# AC_nest.net
KiCad netlist of a schematic drawn in EAGLE
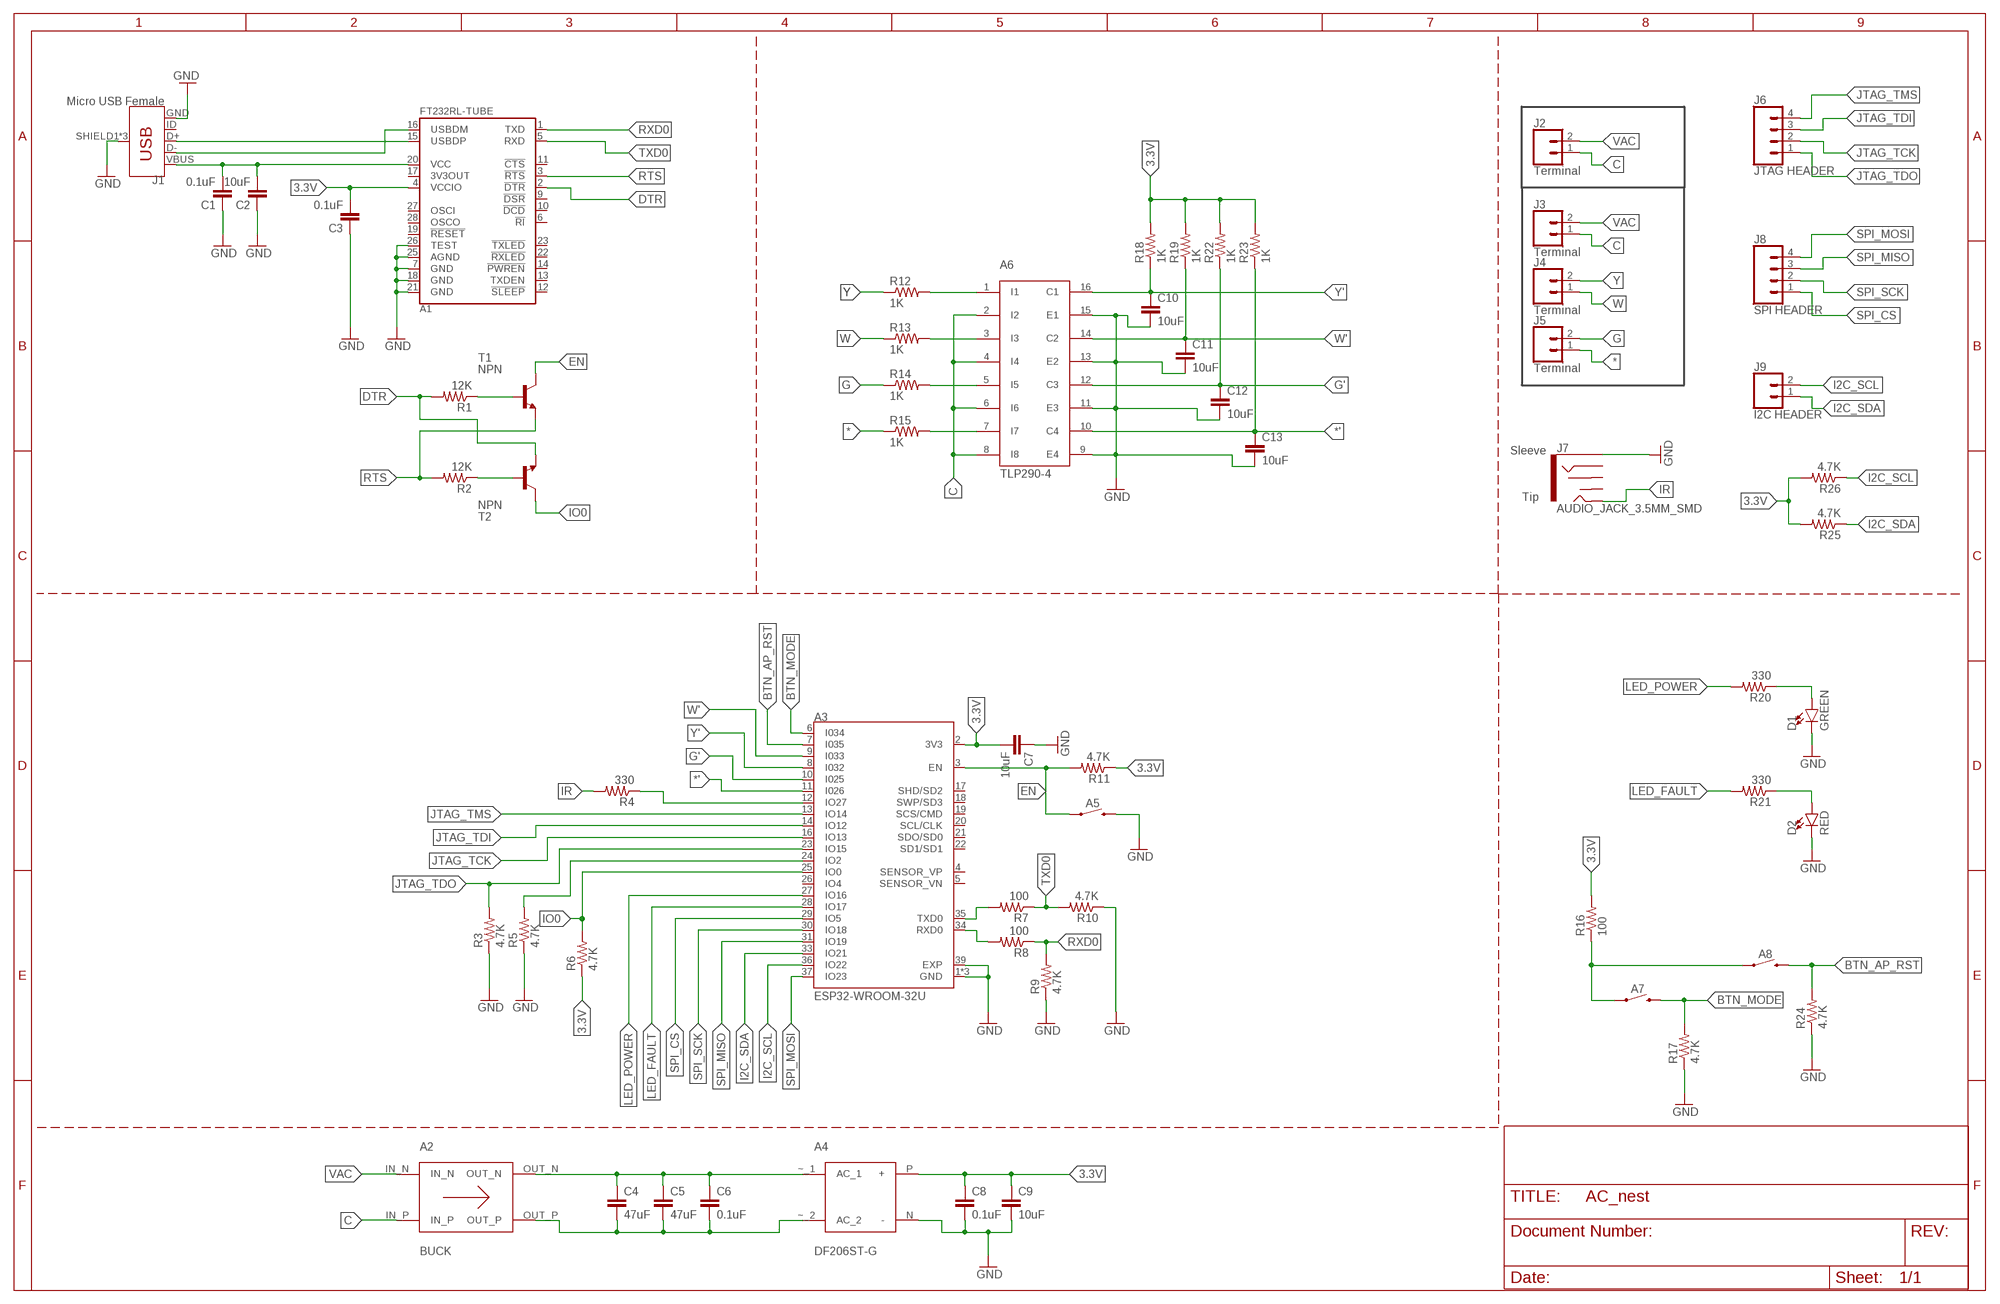
[diagram p0: schematic, sheet 1]

(export (version "E")
  (design (tool "Eeschema 10.0.6"))
  (components
    (comp (ref "A1")
      (value "FT232RL")
      (footprint "eagle-import:SSOP28-LD")
      (fields (field (name "MF") "FTDI,") (field (name "MP") "FT232RL-TUBE"))
      (libsource (lib "eagle-import") (part "FT232RL"))
    )
    (comp (ref "A2")
      (value "BUCK")
      (footprint "eagle-import:BUCK")
      (libsource (lib "eagle-import") (part "BUCK"))
    )
    (comp (ref "A3")
      (value "ESP32-WROOM-32U")
      (footprint "eagle-import:XCVR_ESP32-WROOM-32U")
      (fields (field (name "MF") "Espressif Systems"))
      (libsource (lib "eagle-import") (part "ESP32-WROOM-32U"))
    )
    (comp (ref "A4")
      (value "DF206ST-G")
      (footprint "eagle-import:DF206ST-G")
      (libsource (lib "eagle-import") (part "DF206ST-G"))
    )
    (comp (ref "A5")
      (value "TL3302AF180QJ")
      (footprint "eagle-import:TL3302AF180QJ")
      (libsource (lib "eagle-import") (part "TL3302AF180QJ"))
    )
    (comp (ref "A6")
      (value "TLP290-4")
      (footprint "eagle-import:TLP290-4")
      (libsource (lib "eagle-import") (part "TLP290-4"))
    )
    (comp (ref "A7")
      (value "TL3302AF180QJ")
      (footprint "eagle-import:TL3302AF180QJ")
      (libsource (lib "eagle-import") (part "TL3302AF180QJ"))
    )
    (comp (ref "A8")
      (value "TL3302AF180QJ")
      (footprint "eagle-import:TL3302AF180QJ")
      (libsource (lib "eagle-import") (part "TL3302AF180QJ"))
    )
    (comp (ref "C1")
      (value "0.1uF")
      (footprint "eagle-import:C0603")
      (libsource (lib "eagle-import") (part "C-EUC0603"))
    )
    (comp (ref "C2")
      (value "10uF")
      (footprint "eagle-import:C0603")
      (libsource (lib "eagle-import") (part "C-EUC0603"))
    )
    (comp (ref "C3")
      (value "0.1uF")
      (footprint "eagle-import:C0603")
      (libsource (lib "eagle-import") (part "C-EUC0603"))
    )
    (comp (ref "C4")
      (value "47uF")
      (footprint "eagle-import:C0603")
      (libsource (lib "eagle-import") (part "C-EUC0603"))
    )
    (comp (ref "C5")
      (value "47uF")
      (footprint "eagle-import:C0603")
      (libsource (lib "eagle-import") (part "C-EUC0603"))
    )
    (comp (ref "C6")
      (value "0.1uF")
      (footprint "eagle-import:C0603")
      (libsource (lib "eagle-import") (part "C-EUC0603"))
    )
    (comp (ref "C7")
      (value "10uF")
      (footprint "eagle-import:C0603")
      (libsource (lib "eagle-import") (part "C-EUC0603"))
    )
    (comp (ref "C8")
      (value "0.1uF")
      (footprint "eagle-import:C0603")
      (libsource (lib "eagle-import") (part "C-EUC0603"))
    )
    (comp (ref "C9")
      (value "10uF")
      (footprint "eagle-import:C0603")
      (libsource (lib "eagle-import") (part "C-EUC0603"))
    )
    (comp (ref "C10")
      (value "10uF")
      (footprint "eagle-import:C0603")
      (libsource (lib "eagle-import") (part "C-EUC0603"))
    )
    (comp (ref "C11")
      (value "10uF")
      (footprint "eagle-import:C0603")
      (libsource (lib "eagle-import") (part "C-EUC0603"))
    )
    (comp (ref "C12")
      (value "10uF")
      (footprint "eagle-import:C0603")
      (libsource (lib "eagle-import") (part "C-EUC0603"))
    )
    (comp (ref "C13")
      (value "10uF")
      (footprint "eagle-import:C0603")
      (libsource (lib "eagle-import") (part "C-EUC0603"))
    )
    (comp (ref "D1")
      (value "GREEN")
      (footprint "eagle-import:LED-0603")
      (libsource (lib "eagle-import") (part "LED-GREEN0603"))
    )
    (comp (ref "D2")
      (value "RED")
      (footprint "eagle-import:LED-0603")
      (libsource (lib "eagle-import") (part "LED-RED0603"))
    )
    (comp (ref "J1")
      (value "Micro USB Female")
      (footprint "eagle-import:USB-B-MICRO-SMD")
      (libsource (lib "eagle-import") (part "USB_MICRO-B_FEMALE-SMT"))
    )
    (comp (ref "J2")
      (value "Terminal")
      (footprint "eagle-import:SCREWTERMINAL-3.5MM-2")
      (libsource (lib "eagle-import") (part "CONN_023.5MM"))
    )
    (comp (ref "J3")
      (value "Terminal")
      (footprint "eagle-import:SCREWTERMINAL-3.5MM-2")
      (libsource (lib "eagle-import") (part "CONN_023.5MM"))
    )
    (comp (ref "J4")
      (value "Terminal")
      (footprint "eagle-import:SCREWTERMINAL-3.5MM-2")
      (libsource (lib "eagle-import") (part "CONN_023.5MM"))
    )
    (comp (ref "J5")
      (value "Terminal")
      (footprint "eagle-import:SCREWTERMINAL-3.5MM-2")
      (libsource (lib "eagle-import") (part "CONN_023.5MM"))
    )
    (comp (ref "J6")
      (value "JTAG HEADER")
      (footprint "eagle-import:1X04")
      (libsource (lib "eagle-import") (part "CONN_04"))
    )
    (comp (ref "J7")
      (value "AUDIO_JACK_3.5MM_SMD")
      (footprint "eagle-import:AUDIO-JACK-3.5MM-SMD")
      (libsource (lib "eagle-import") (part "AUDIO_JACK_3.5MM_SMD"))
    )
    (comp (ref "J8")
      (value "SPI HEADER")
      (footprint "eagle-import:1X04")
      (libsource (lib "eagle-import") (part "SparkFun-Connectors_513_CONN_04"))
    )
    (comp (ref "J9")
      (value "I2C HEADER")
      (footprint "eagle-import:1X02")
      (libsource (lib "eagle-import") (part "CONN_02"))
    )
    (comp (ref "R1")
      (value "12K")
      (footprint "eagle-import:R0603")
      (libsource (lib "eagle-import") (part "R-US_R0603"))
    )
    (comp (ref "R2")
      (value "12K")
      (footprint "eagle-import:R0603")
      (libsource (lib "eagle-import") (part "R-US_R0603"))
    )
    (comp (ref "R3")
      (value "4.7K")
      (footprint "eagle-import:R0603")
      (libsource (lib "eagle-import") (part "R-US_R0603"))
    )
    (comp (ref "R4")
      (value "330")
      (footprint "eagle-import:R0603")
      (libsource (lib "eagle-import") (part "R-US_R0603"))
    )
    (comp (ref "R5")
      (value "4.7K")
      (footprint "eagle-import:R0603")
      (libsource (lib "eagle-import") (part "R-US_R0603"))
    )
    (comp (ref "R6")
      (value "4.7K")
      (footprint "eagle-import:R0603")
      (libsource (lib "eagle-import") (part "R-US_R0603"))
    )
    (comp (ref "R7")
      (value "100")
      (footprint "eagle-import:R0603")
      (libsource (lib "eagle-import") (part "R-US_R0603"))
    )
    (comp (ref "R8")
      (value "100")
      (footprint "eagle-import:R0603")
      (libsource (lib "eagle-import") (part "R-US_R0603"))
    )
    (comp (ref "R9")
      (value "4.7K")
      (footprint "eagle-import:R0603")
      (libsource (lib "eagle-import") (part "R-US_R0603"))
    )
    (comp (ref "R10")
      (value "4.7K")
      (footprint "eagle-import:R0603")
      (libsource (lib "eagle-import") (part "R-US_R0603"))
    )
    (comp (ref "R11")
      (value "4.7K")
      (footprint "eagle-import:R0603")
      (libsource (lib "eagle-import") (part "R-US_R0603"))
    )
    (comp (ref "R12")
      (value "1K")
      (footprint "eagle-import:R0603")
      (libsource (lib "eagle-import") (part "R-US_R0603"))
    )
    (comp (ref "R13")
      (value "1K")
      (footprint "eagle-import:R0603")
      (libsource (lib "eagle-import") (part "R-US_R0603"))
    )
    (comp (ref "R14")
      (value "1K")
      (footprint "eagle-import:R0603")
      (libsource (lib "eagle-import") (part "R-US_R0603"))
    )
    (comp (ref "R15")
      (value "1K")
      (footprint "eagle-import:R0603")
      (libsource (lib "eagle-import") (part "R-US_R0603"))
    )
    (comp (ref "R16")
      (value "100")
      (footprint "eagle-import:R0603")
      (libsource (lib "eagle-import") (part "R-US_R0603"))
    )
    (comp (ref "R17")
      (value "4.7K")
      (footprint "eagle-import:R0603")
      (libsource (lib "eagle-import") (part "R-US_R0603"))
    )
    (comp (ref "R18")
      (value "1K")
      (footprint "eagle-import:R0603")
      (libsource (lib "eagle-import") (part "R-US_R0603"))
    )
    (comp (ref "R19")
      (value "1K")
      (footprint "eagle-import:R0603")
      (libsource (lib "eagle-import") (part "R-US_R0603"))
    )
    (comp (ref "R20")
      (value "330")
      (footprint "eagle-import:R0603")
      (libsource (lib "eagle-import") (part "R-US_R0603"))
    )
    (comp (ref "R21")
      (value "330")
      (footprint "eagle-import:R0603")
      (libsource (lib "eagle-import") (part "R-US_R0603"))
    )
    (comp (ref "R22")
      (value "1K")
      (footprint "eagle-import:R0603")
      (libsource (lib "eagle-import") (part "R-US_R0603"))
    )
    (comp (ref "R23")
      (value "1K")
      (footprint "eagle-import:R0603")
      (libsource (lib "eagle-import") (part "R-US_R0603"))
    )
    (comp (ref "R24")
      (value "4.7K")
      (footprint "eagle-import:R0603")
      (libsource (lib "eagle-import") (part "R-US_R0603"))
    )
    (comp (ref "R25")
      (value "4.7K")
      (footprint "eagle-import:R0603")
      (libsource (lib "eagle-import") (part "R-US_R0603"))
    )
    (comp (ref "R26")
      (value "4.7K")
      (footprint "eagle-import:R0603")
      (libsource (lib "eagle-import") (part "R-US_R0603"))
    )
    (comp (ref "T1")
      (value "NPN")
      (footprint "eagle-import:SOT23-EBC")
      (libsource (lib "eagle-import") (part "-NPN-SOT23-EBC"))
    )
    (comp (ref "T2")
      (value "NPN")
      (footprint "eagle-import:SOT23-EBC")
      (libsource (lib "eagle-import") (part "-NPN-SOT23-EBC"))
    )
  )
  (nets
    (net (code "1") (name "*") (class "Default")
      (node (ref "J5") (pin "1") (pinfunction "1_1") (pintype "passive"))
      (node (ref "R15") (pin "1") (pinfunction "1_1") (pintype "passive"))
    )
    (net (code "2") (name "*'") (class "Default")
      (node (ref "A3") (pin "11") (pinfunction "I026_11") (pintype "bidirectional"))
      (node (ref "A6") (pin "10") (pinfunction "C4_10") (pintype "bidirectional"))
      (node (ref "C13") (pin "1") (pinfunction "1_1") (pintype "passive"))
      (node (ref "R23") (pin "1") (pinfunction "1_1") (pintype "passive"))
    )
    (net (code "3") (name "/3V3OUT") (class "Default")
      (node (ref "A1") (pin "17") (pinfunction "3V3OUT_17") (pintype "power_in"))
    )
    (net (code "4") (name "3.3V") (class "Default")
      (node (ref "A1") (pin "4") (pinfunction "VCCIO_4") (pintype "power_in"))
      (node (ref "A3") (pin "2") (pinfunction "3V3_2") (pintype "power_in"))
      (node (ref "A4") (pin "P") (pinfunction "+_P") (pintype "bidirectional"))
      (node (ref "C3") (pin "2") (pinfunction "2_2") (pintype "passive"))
      (node (ref "C7") (pin "2") (pinfunction "2_2") (pintype "passive"))
      (node (ref "C8") (pin "1") (pinfunction "1_1") (pintype "passive"))
      (node (ref "C9") (pin "1") (pinfunction "1_1") (pintype "passive"))
      (node (ref "R11") (pin "1") (pinfunction "1_1") (pintype "passive"))
      (node (ref "R16") (pin "2") (pinfunction "2_2") (pintype "passive"))
      (node (ref "R18") (pin "2") (pinfunction "2_2") (pintype "passive"))
      (node (ref "R19") (pin "2") (pinfunction "2_2") (pintype "passive"))
      (node (ref "R22") (pin "2") (pinfunction "2_2") (pintype "passive"))
      (node (ref "R23") (pin "2") (pinfunction "2_2") (pintype "passive"))
      (node (ref "R25") (pin "2") (pinfunction "2_2") (pintype "passive"))
      (node (ref "R26") (pin "2") (pinfunction "2_2") (pintype "passive"))
      (node (ref "R6") (pin "1") (pinfunction "1_1") (pintype "passive"))
    )
    (net (code "5") (name "BTN_AP_RST") (class "Default")
      (node (ref "A3") (pin "7") (pinfunction "I035_7") (pintype "input"))
      (node (ref "A8") (pin "2") (pinfunction "2_2") (pintype "passive"))
      (node (ref "R24") (pin "2") (pinfunction "2_2") (pintype "passive"))
    )
    (net (code "6") (name "BTN_MODE") (class "Default")
      (node (ref "A3") (pin "6") (pinfunction "I034_6") (pintype "input"))
      (node (ref "A7") (pin "2") (pinfunction "2_2") (pintype "passive"))
      (node (ref "R17") (pin "2") (pinfunction "2_2") (pintype "passive"))
    )
    (net (code "7") (name "C") (class "Default")
      (node (ref "A2") (pin "IN_P") (pinfunction "IN_P_IN_P") (pintype "bidirectional"))
      (node (ref "A6") (pin "2") (pinfunction "I2_2") (pintype "bidirectional"))
      (node (ref "A6") (pin "4") (pinfunction "I4_4") (pintype "bidirectional"))
      (node (ref "A6") (pin "6") (pinfunction "I6_6") (pintype "bidirectional"))
      (node (ref "A6") (pin "8") (pinfunction "I8_8") (pintype "bidirectional"))
      (node (ref "J2") (pin "1") (pinfunction "1_1") (pintype "passive"))
      (node (ref "J3") (pin "1") (pinfunction "1_1") (pintype "passive"))
    )
    (net (code "8") (name "DTR") (class "Default")
      (node (ref "A1") (pin "2") (pinfunction "~{DTR}_2") (pintype "output"))
      (node (ref "R1") (pin "2") (pinfunction "2_2") (pintype "passive"))
      (node (ref "T2") (pin "E") (pinfunction "E_E") (pintype "passive"))
    )
    (net (code "9") (name "EN") (class "Default")
      (node (ref "A3") (pin "3") (pinfunction "EN_3") (pintype "input"))
      (node (ref "A5") (pin "1") (pinfunction "1_1") (pintype "passive"))
      (node (ref "R11") (pin "2") (pinfunction "2_2") (pintype "passive"))
      (node (ref "T1") (pin "C") (pinfunction "C_C") (pintype "passive"))
    )
    (net (code "10") (name "G") (class "Default")
      (node (ref "J5") (pin "2") (pinfunction "2_2") (pintype "passive"))
      (node (ref "R14") (pin "1") (pinfunction "1_1") (pintype "passive"))
    )
    (net (code "11") (name "G'") (class "Default")
      (node (ref "A3") (pin "10") (pinfunction "I025_10") (pintype "bidirectional"))
      (node (ref "A6") (pin "12") (pinfunction "C3_12") (pintype "bidirectional"))
      (node (ref "C12") (pin "1") (pinfunction "1_1") (pintype "passive"))
      (node (ref "R22") (pin "1") (pinfunction "1_1") (pintype "passive"))
    )
    (net (code "12") (name "GND") (class "Default")
      (node (ref "A1") (pin "18") (pinfunction "GND_18") (pintype "power_in"))
      (node (ref "A1") (pin "21") (pinfunction "GND_21") (pintype "power_in"))
      (node (ref "A1") (pin "25") (pinfunction "AGND_25") (pintype "power_in"))
      (node (ref "A1") (pin "26") (pinfunction "TEST_26") (pintype "input"))
      (node (ref "A1") (pin "7") (pinfunction "GND_7") (pintype "power_in"))
      (node (ref "A3") (pin "1") (pinfunction "GND_1") (pintype "power_in"))
      (node (ref "A3") (pin "15") (pinfunction "GND_15") (pintype "power_in"))
      (node (ref "A3") (pin "38") (pinfunction "GND_38") (pintype "power_in"))
      (node (ref "A3") (pin "39") (pinfunction "EXP_39") (pintype "power_in"))
      (node (ref "A4") (pin "N") (pinfunction "-_N") (pintype "bidirectional"))
      (node (ref "A5") (pin "2") (pinfunction "2_2") (pintype "passive"))
      (node (ref "A6") (pin "11") (pinfunction "E3_11") (pintype "bidirectional"))
      (node (ref "A6") (pin "13") (pinfunction "E2_13") (pintype "bidirectional"))
      (node (ref "A6") (pin "15") (pinfunction "E1_15") (pintype "bidirectional"))
      (node (ref "A6") (pin "9") (pinfunction "E4_9") (pintype "bidirectional"))
      (node (ref "C1") (pin "1") (pinfunction "1_1") (pintype "passive"))
      (node (ref "C10") (pin "2") (pinfunction "2_2") (pintype "passive"))
      (node (ref "C11") (pin "2") (pinfunction "2_2") (pintype "passive"))
      (node (ref "C12") (pin "2") (pinfunction "2_2") (pintype "passive"))
      (node (ref "C13") (pin "2") (pinfunction "2_2") (pintype "passive"))
      (node (ref "C2") (pin "1") (pinfunction "1_1") (pintype "passive"))
      (node (ref "C3") (pin "1") (pinfunction "1_1") (pintype "passive"))
      (node (ref "C7") (pin "1") (pinfunction "1_1") (pintype "passive"))
      (node (ref "C8") (pin "2") (pinfunction "2_2") (pintype "passive"))
      (node (ref "C9") (pin "2") (pinfunction "2_2") (pintype "passive"))
      (node (ref "D1") (pin "C") (pinfunction "C_C") (pintype "passive"))
      (node (ref "D2") (pin "C") (pinfunction "C_C") (pintype "passive"))
      (node (ref "J1") (pin "GND") (pinfunction "GND_GND") (pintype "power_in"))
      (node (ref "J1") (pin "SHIELD1") (pinfunction "SHIELD_SHIELD1") (pintype "bidirectional"))
      (node (ref "J1") (pin "SHIELD2") (pinfunction "SHIELD_SHIELD2") (pintype "bidirectional"))
      (node (ref "J1") (pin "SHIELD3") (pinfunction "SHIELD_SHIELD3") (pintype "bidirectional"))
      (node (ref "J7") (pin "SLEEVE") (pinfunction "SLEEVE_SLEEVE") (pintype "bidirectional"))
      (node (ref "R10") (pin "1") (pinfunction "1_1") (pintype "passive"))
      (node (ref "R17") (pin "1") (pinfunction "1_1") (pintype "passive"))
      (node (ref "R24") (pin "1") (pinfunction "1_1") (pintype "passive"))
      (node (ref "R3") (pin "1") (pinfunction "1_1") (pintype "passive"))
      (node (ref "R5") (pin "1") (pinfunction "1_1") (pintype "passive"))
      (node (ref "R9") (pin "1") (pinfunction "1_1") (pintype "passive"))
    )
    (net (code "13") (name "I2C_SCL") (class "Default")
      (node (ref "A3") (pin "36") (pinfunction "IO22_36") (pintype "bidirectional"))
      (node (ref "J9") (pin "2") (pinfunction "2_2") (pintype "passive"))
      (node (ref "R26") (pin "1") (pinfunction "1_1") (pintype "passive"))
    )
    (net (code "14") (name "I2C_SDA") (class "Default")
      (node (ref "A3") (pin "33") (pinfunction "IO21_33") (pintype "bidirectional"))
      (node (ref "J9") (pin "1") (pinfunction "1_1") (pintype "passive"))
      (node (ref "R25") (pin "1") (pinfunction "1_1") (pintype "passive"))
    )
    (net (code "15") (name "IO0") (class "Default")
      (node (ref "A3") (pin "25") (pinfunction "IO0_25") (pintype "bidirectional"))
      (node (ref "R6") (pin "2") (pinfunction "2_2") (pintype "passive"))
      (node (ref "T2") (pin "C") (pinfunction "C_C") (pintype "passive"))
    )
    (net (code "16") (name "IR") (class "Default")
      (node (ref "J7") (pin "TIP") (pinfunction "TIP_TIP") (pintype "bidirectional"))
      (node (ref "R4") (pin "2") (pinfunction "2_2") (pintype "passive"))
    )
    (net (code "17") (name "JTAG_TCK") (class "Default")
      (node (ref "A3") (pin "16") (pinfunction "IO13_16") (pintype "bidirectional"))
      (node (ref "J6") (pin "2") (pinfunction "2_2") (pintype "passive"))
    )
    (net (code "18") (name "JTAG_TDI") (class "Default")
      (node (ref "A3") (pin "14") (pinfunction "IO12_14") (pintype "bidirectional"))
      (node (ref "J6") (pin "3") (pinfunction "3_3") (pintype "passive"))
    )
    (net (code "19") (name "JTAG_TDO") (class "Default")
      (node (ref "A3") (pin "23") (pinfunction "IO15_23") (pintype "bidirectional"))
      (node (ref "J6") (pin "1") (pinfunction "1_1") (pintype "passive"))
      (node (ref "R3") (pin "2") (pinfunction "2_2") (pintype "passive"))
    )
    (net (code "20") (name "JTAG_TMS") (class "Default")
      (node (ref "A3") (pin "13") (pinfunction "IO14_13") (pintype "bidirectional"))
      (node (ref "J6") (pin "4") (pinfunction "4_4") (pintype "passive"))
    )
    (net (code "21") (name "LED_FAULT") (class "Default")
      (node (ref "A3") (pin "28") (pinfunction "IO17_28") (pintype "bidirectional"))
      (node (ref "R21") (pin "2") (pinfunction "2_2") (pintype "passive"))
    )
    (net (code "22") (name "LED_POWER") (class "Default")
      (node (ref "A3") (pin "27") (pinfunction "IO16_27") (pintype "bidirectional"))
      (node (ref "R20") (pin "2") (pinfunction "2_2") (pintype "passive"))
    )
    (net (code "23") (name "Net-(A1-USBDM)") (class "Default")
      (node (ref "A1") (pin "16") (pinfunction "USBDM_16") (pintype "bidirectional"))
      (node (ref "J1") (pin "D-") (pinfunction "D-_D-") (pintype "bidirectional"))
    )
    (net (code "24") (name "Net-(A1-USBDP)") (class "Default")
      (node (ref "A1") (pin "15") (pinfunction "USBDP_15") (pintype "bidirectional"))
      (node (ref "J1") (pin "D+") (pinfunction "D+_D+") (pintype "bidirectional"))
    )
    (net (code "25") (name "Net-(A1-VCC)") (class "Default")
      (node (ref "A1") (pin "20") (pinfunction "VCC_20") (pintype "power_in"))
      (node (ref "C1") (pin "2") (pinfunction "2_2") (pintype "passive"))
      (node (ref "C2") (pin "2") (pinfunction "2_2") (pintype "passive"))
      (node (ref "J1") (pin "VBUS") (pinfunction "VBUS_VBUS") (pintype "power_in"))
    )
    (net (code "26") (name "Net-(A3-IO2)") (class "Default")
      (node (ref "A3") (pin "24") (pinfunction "IO2_24") (pintype "bidirectional"))
      (node (ref "R5") (pin "2") (pinfunction "2_2") (pintype "passive"))
    )
    (net (code "27") (name "Net-(A3-IO27)") (class "Default")
      (node (ref "A3") (pin "12") (pinfunction "IO27_12") (pintype "bidirectional"))
      (node (ref "R4") (pin "1") (pinfunction "1_1") (pintype "passive"))
    )
    (net (code "28") (name "Net-(A3-RXD0)") (class "Default")
      (node (ref "A3") (pin "34") (pinfunction "RXD0_34") (pintype "bidirectional"))
      (node (ref "R8") (pin "2") (pinfunction "2_2") (pintype "passive"))
    )
    (net (code "29") (name "Net-(A3-TXD0)") (class "Default")
      (node (ref "A3") (pin "35") (pinfunction "TXD0_35") (pintype "bidirectional"))
      (node (ref "R7") (pin "2") (pinfunction "2_2") (pintype "passive"))
    )
    (net (code "30") (name "Net-(A4-AC_1)") (class "Default")
      (node (ref "A2") (pin "OUT_N") (pinfunction "OUT_N_OUT_N") (pintype "bidirectional"))
      (node (ref "A4") (pin "~_1") (pinfunction "AC_1_~_1") (pintype "bidirectional"))
      (node (ref "C4") (pin "1") (pinfunction "1_1") (pintype "passive"))
      (node (ref "C5") (pin "1") (pinfunction "1_1") (pintype "passive"))
      (node (ref "C6") (pin "1") (pinfunction "1_1") (pintype "passive"))
    )
    (net (code "31") (name "Net-(A4-AC_2)") (class "Default")
      (node (ref "A2") (pin "OUT_P") (pinfunction "OUT_P_OUT_P") (pintype "bidirectional"))
      (node (ref "A4") (pin "~_2") (pinfunction "AC_2_~_2") (pintype "bidirectional"))
      (node (ref "C4") (pin "2") (pinfunction "2_2") (pintype "passive"))
      (node (ref "C5") (pin "2") (pinfunction "2_2") (pintype "passive"))
      (node (ref "C6") (pin "2") (pinfunction "2_2") (pintype "passive"))
    )
    (net (code "32") (name "Net-(A6-I1)") (class "Default")
      (node (ref "A6") (pin "1") (pinfunction "I1_1") (pintype "bidirectional"))
      (node (ref "R12") (pin "2") (pinfunction "2_2") (pintype "passive"))
    )
    (net (code "33") (name "Net-(A6-I3)") (class "Default")
      (node (ref "A6") (pin "3") (pinfunction "I3_3") (pintype "bidirectional"))
      (node (ref "R13") (pin "2") (pinfunction "2_2") (pintype "passive"))
    )
    (net (code "34") (name "Net-(A6-I5)") (class "Default")
      (node (ref "A6") (pin "5") (pinfunction "I5_5") (pintype "bidirectional"))
      (node (ref "R14") (pin "2") (pinfunction "2_2") (pintype "passive"))
    )
    (net (code "35") (name "Net-(A6-I7)") (class "Default")
      (node (ref "A6") (pin "7") (pinfunction "I7_7") (pintype "bidirectional"))
      (node (ref "R15") (pin "2") (pinfunction "2_2") (pintype "passive"))
    )
    (net (code "36") (name "Net-(A7-Pad1)") (class "Default")
      (node (ref "A7") (pin "1") (pinfunction "1_1") (pintype "passive"))
      (node (ref "A8") (pin "1") (pinfunction "1_1") (pintype "passive"))
      (node (ref "R16") (pin "1") (pinfunction "1_1") (pintype "passive"))
    )
    (net (code "37") (name "Net-(D1-PadA)") (class "Default")
      (node (ref "D1") (pin "A") (pinfunction "A_A") (pintype "passive"))
      (node (ref "R20") (pin "1") (pinfunction "1_1") (pintype "passive"))
    )
    (net (code "38") (name "Net-(D2-PadA)") (class "Default")
      (node (ref "D2") (pin "A") (pinfunction "A_A") (pintype "passive"))
      (node (ref "R21") (pin "1") (pinfunction "1_1") (pintype "passive"))
    )
    (net (code "39") (name "Net-(R1-Pad1)") (class "Default")
      (node (ref "R1") (pin "1") (pinfunction "1_1") (pintype "passive"))
      (node (ref "T1") (pin "B") (pinfunction "B_B") (pintype "passive"))
    )
    (net (code "40") (name "Net-(R2-Pad1)") (class "Default")
      (node (ref "R2") (pin "1") (pinfunction "1_1") (pintype "passive"))
      (node (ref "T2") (pin "B") (pinfunction "B_B") (pintype "passive"))
    )
    (net (code "41") (name "RTS") (class "Default")
      (node (ref "A1") (pin "3") (pinfunction "~{RTS}_3") (pintype "output"))
      (node (ref "R2") (pin "2") (pinfunction "2_2") (pintype "passive"))
      (node (ref "T1") (pin "E") (pinfunction "E_E") (pintype "passive"))
    )
    (net (code "42") (name "RXD0") (class "Default")
      (node (ref "A1") (pin "1") (pinfunction "TXD_1") (pintype "output"))
      (node (ref "R8") (pin "1") (pinfunction "1_1") (pintype "passive"))
      (node (ref "R9") (pin "2") (pinfunction "2_2") (pintype "passive"))
    )
    (net (code "43") (name "SPI_CS") (class "Default")
      (node (ref "A3") (pin "29") (pinfunction "IO5_29") (pintype "bidirectional"))
      (node (ref "J8") (pin "1") (pinfunction "1_1") (pintype "passive"))
    )
    (net (code "44") (name "SPI_MISO") (class "Default")
      (node (ref "A3") (pin "31") (pinfunction "IO19_31") (pintype "bidirectional"))
      (node (ref "J8") (pin "3") (pinfunction "3_3") (pintype "passive"))
    )
    (net (code "45") (name "SPI_MOSI") (class "Default")
      (node (ref "A3") (pin "37") (pinfunction "IO23_37") (pintype "bidirectional"))
      (node (ref "J8") (pin "4") (pinfunction "4_4") (pintype "passive"))
    )
    (net (code "46") (name "SPI_SCK") (class "Default")
      (node (ref "A3") (pin "30") (pinfunction "IO18_30") (pintype "bidirectional"))
      (node (ref "J8") (pin "2") (pinfunction "2_2") (pintype "passive"))
    )
    (net (code "47") (name "TXD0") (class "Default")
      (node (ref "A1") (pin "5") (pinfunction "RXD_5") (pintype "input"))
      (node (ref "R10") (pin "2") (pinfunction "2_2") (pintype "passive"))
      (node (ref "R7") (pin "1") (pinfunction "1_1") (pintype "passive"))
    )
    (net (code "48") (name "VAC") (class "Default")
      (node (ref "A2") (pin "IN_N") (pinfunction "IN_N_IN_N") (pintype "bidirectional"))
      (node (ref "J2") (pin "2") (pinfunction "2_2") (pintype "passive"))
      (node (ref "J3") (pin "2") (pinfunction "2_2") (pintype "passive"))
    )
    (net (code "49") (name "W") (class "Default")
      (node (ref "J4") (pin "1") (pinfunction "1_1") (pintype "passive"))
      (node (ref "R13") (pin "1") (pinfunction "1_1") (pintype "passive"))
    )
    (net (code "50") (name "W'") (class "Default")
      (node (ref "A3") (pin "9") (pinfunction "I033_9") (pintype "bidirectional"))
      (node (ref "A6") (pin "14") (pinfunction "C2_14") (pintype "bidirectional"))
      (node (ref "C11") (pin "1") (pinfunction "1_1") (pintype "passive"))
      (node (ref "R19") (pin "1") (pinfunction "1_1") (pintype "passive"))
    )
    (net (code "51") (name "Y") (class "Default")
      (node (ref "J4") (pin "2") (pinfunction "2_2") (pintype "passive"))
      (node (ref "R12") (pin "1") (pinfunction "1_1") (pintype "passive"))
    )
    (net (code "52") (name "Y'") (class "Default")
      (node (ref "A3") (pin "8") (pinfunction "I032_8") (pintype "bidirectional"))
      (node (ref "A6") (pin "16") (pinfunction "C1_16") (pintype "bidirectional"))
      (node (ref "C10") (pin "1") (pinfunction "1_1") (pintype "passive"))
      (node (ref "R18") (pin "1") (pinfunction "1_1") (pintype "passive"))
    )
    (net (code "53") (name "unconnected-(A1-OSCI-Pad27)") (class "Default")
      (node (ref "A1") (pin "27") (pinfunction "OSCI_27") (pintype "no_connect"))
    )
    (net (code "54") (name "unconnected-(A1-OSCO-Pad28)") (class "Default")
      (node (ref "A1") (pin "28") (pinfunction "OSCO_28") (pintype "output"))
    )
    (net (code "55") (name "unconnected-(A1-TXDEN-Pad13)") (class "Default")
      (node (ref "A1") (pin "13") (pinfunction "TXDEN_13") (pintype "no_connect"))
    )
    (net (code "56") (name "unconnected-(A1-~{CTS}-Pad11)") (class "Default")
      (node (ref "A1") (pin "11") (pinfunction "~{CTS}_11") (pintype "input"))
    )
    (net (code "57") (name "unconnected-(A1-~{DCD}-Pad10)") (class "Default")
      (node (ref "A1") (pin "10") (pinfunction "~{DCD}_10") (pintype "no_connect"))
    )
    (net (code "58") (name "unconnected-(A1-~{DSR}-Pad9)") (class "Default")
      (node (ref "A1") (pin "9") (pinfunction "~{DSR}_9") (pintype "no_connect"))
    )
    (net (code "59") (name "unconnected-(A1-~{PWREN}-Pad14)") (class "Default")
      (node (ref "A1") (pin "14") (pinfunction "~{PWREN}_14") (pintype "no_connect"))
    )
    (net (code "60") (name "unconnected-(A1-~{RESET}-Pad19)") (class "Default")
      (node (ref "A1") (pin "19") (pinfunction "~{RESET}_19") (pintype "no_connect"))
    )
    (net (code "61") (name "unconnected-(A1-~{RI}-Pad6)") (class "Default")
      (node (ref "A1") (pin "6") (pinfunction "~{RI}_6") (pintype "no_connect"))
    )
    (net (code "62") (name "unconnected-(A1-~{RXLED}-Pad22)") (class "Default")
      (node (ref "A1") (pin "22") (pinfunction "~{RXLED}_22") (pintype "input"))
    )
    (net (code "63") (name "unconnected-(A1-~{SLEEP}-Pad12)") (class "Default")
      (node (ref "A1") (pin "12") (pinfunction "~{SLEEP}_12") (pintype "no_connect"))
    )
    (net (code "64") (name "unconnected-(A1-~{TXLED}-Pad23)") (class "Default")
      (node (ref "A1") (pin "23") (pinfunction "~{TXLED}_23") (pintype "input"))
    )
    (net (code "65") (name "unconnected-(A3-IO4-Pad26)") (class "Default")
      (node (ref "A3") (pin "26") (pinfunction "IO4_26") (pintype "bidirectional"))
    )
    (net (code "66") (name "unconnected-(A3-SCL{slash}CLK-Pad20)") (class "Default")
      (node (ref "A3") (pin "20") (pinfunction "SCL/CLK_20") (pintype "bidirectional"))
    )
    (net (code "67") (name "unconnected-(A3-SCS{slash}CMD-Pad19)") (class "Default")
      (node (ref "A3") (pin "19") (pinfunction "SCS/CMD_19") (pintype "bidirectional"))
    )
    (net (code "68") (name "unconnected-(A3-SD1{slash}SD1-Pad22)") (class "Default")
      (node (ref "A3") (pin "22") (pinfunction "SD1/SD1_22") (pintype "bidirectional"))
    )
    (net (code "69") (name "unconnected-(A3-SDO{slash}SD0-Pad21)") (class "Default")
      (node (ref "A3") (pin "21") (pinfunction "SDO/SD0_21") (pintype "bidirectional"))
    )
    (net (code "70") (name "unconnected-(A3-SENSOR_VN-Pad5)") (class "Default")
      (node (ref "A3") (pin "5") (pinfunction "SENSOR_VN_5") (pintype "input"))
    )
    (net (code "71") (name "unconnected-(A3-SENSOR_VP-Pad4)") (class "Default")
      (node (ref "A3") (pin "4") (pinfunction "SENSOR_VP_4") (pintype "input"))
    )
    (net (code "72") (name "unconnected-(A3-SHD{slash}SD2-Pad17)") (class "Default")
      (node (ref "A3") (pin "17") (pinfunction "SHD/SD2_17") (pintype "bidirectional"))
    )
    (net (code "73") (name "unconnected-(A3-SWP{slash}SD3-Pad18)") (class "Default")
      (node (ref "A3") (pin "18") (pinfunction "SWP/SD3_18") (pintype "bidirectional"))
    )
    (net (code "74") (name "unconnected-(J1-PadID)") (class "Default")
      (node (ref "J1") (pin "ID") (pinfunction "ID_ID") (pintype "bidirectional"))
    )
    (net (code "75") (name "unconnected-(J7-PadRING)") (class "Default")
      (node (ref "J7") (pin "RING") (pinfunction "RING_RING") (pintype "bidirectional"))
    )
    (net (code "76") (name "unconnected-(J7-PadRSH)") (class "Default")
      (node (ref "J7") (pin "RSH") (pinfunction "RSH_RSH") (pintype "bidirectional"))
    )
    (net (code "77") (name "unconnected-(J7-PadTSH)") (class "Default")
      (node (ref "J7") (pin "TSH") (pinfunction "TSH_TSH") (pintype "bidirectional"))
    )
  )
)
